# DAU_Kupplung_1_phasig_V1_16.net
KiCad netlist of a schematic drawn in Altium Designer
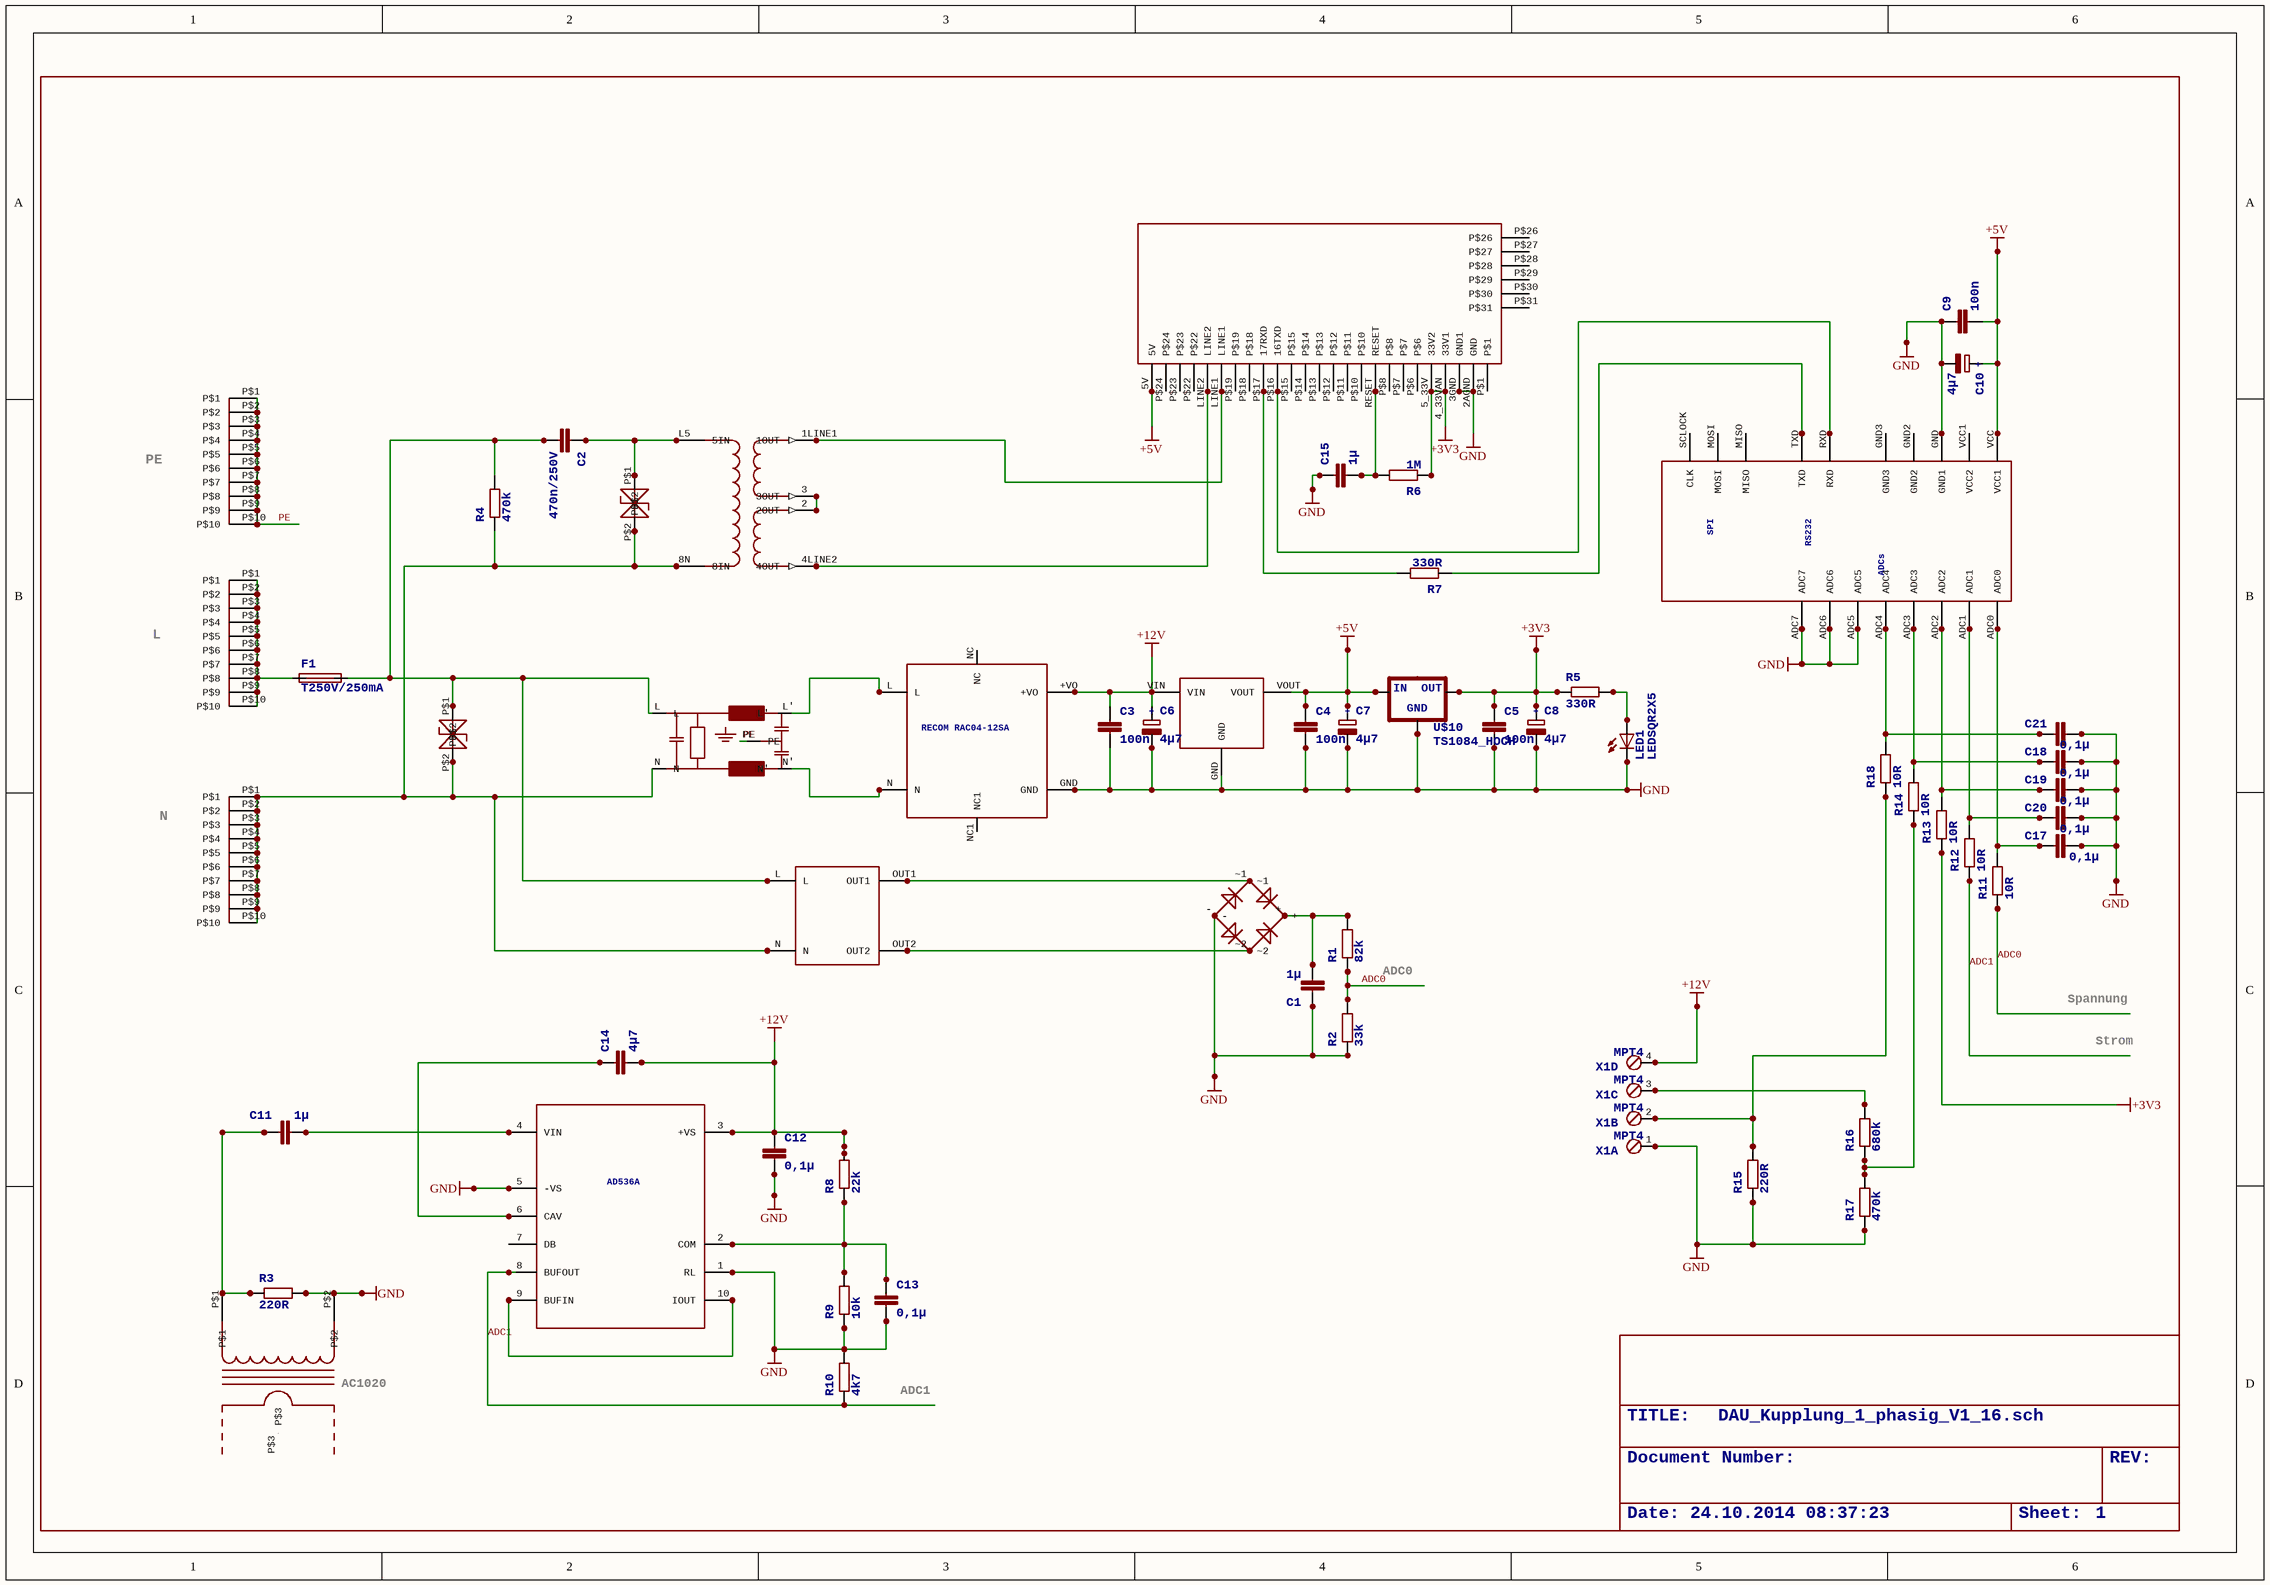
[diagram p0: DAU_Kupplung_1_phasig_V1_16.SchDoc]

(export (version "E")
  (design (tool "Eeschema 10.0.6"))
  (components
    (comp (ref "AC1020") (value "AC1010") (footprint "AC1010") (libsource (lib "ADS") (part "AC1010")))
    (comp (ref "C1")
      (value "1µ")
      (footprint "C2.5-3")
      (description "<B>CAPACITOR</B><p>\nnaming: grid - package width")
      (libsource (lib "capacitor-wima") (part "C2,5-3"))
    )
    (comp (ref "C2")
      (value "470n/250V")
      (footprint "C150-072X183")
      (description "<B>CAPACITOR</B>, European symbol")
      (libsource (lib "resistor") (part "C-EU150-072X183"))
    )
    (comp (ref "C3")
      (value "100n")
      (footprint "C0805")
      (description "<B>CAPACITOR</B>, European symbol")
      (libsource (lib "") (part "C-EUC0805_1"))
    )
    (comp (ref "C4")
      (value "100n")
      (footprint "C0805")
      (description "<B>CAPACITOR</B>, European symbol")
      (libsource (lib "") (part "C-EUC0805_1"))
    )
    (comp (ref "C5")
      (value "100n")
      (footprint "C0805")
      (description "<B>CAPACITOR</B>, European symbol")
      (libsource (lib "") (part "C-EUC0805_1"))
    )
    (comp (ref "C6")
      (value "4µ7")
      (footprint "E2-4")
      (description "<B>POLARIZED CAPACITOR</B>, European symbol")
      (fields (field (name "+") "+"))
      (libsource (lib "rcl") (part "CPOL-EUE2-4"))
    )
    (comp (ref "C7")
      (value "4µ7")
      (footprint "E2-4")
      (description "<B>POLARIZED CAPACITOR</B>, European symbol")
      (fields (field (name "+") "+"))
      (libsource (lib "rcl") (part "CPOL-EUE2-4"))
    )
    (comp (ref "C8")
      (value "4µ7")
      (footprint "E2-4")
      (description "<B>POLARIZED CAPACITOR</B>, European symbol")
      (fields (field (name "+") "+"))
      (libsource (lib "rcl") (part "CPOL-EUE2-4"))
    )
    (comp (ref "C9")
      (value "100n")
      (footprint "C0805")
      (description "<B>CAPACITOR</B>, European symbol")
      (libsource (lib "") (part "C-EUC0805_1"))
    )
    (comp (ref "C10")
      (value "4µ7")
      (footprint "E2-4")
      (description "<B>POLARIZED CAPACITOR</B>, European symbol")
      (fields (field (name "+") "+"))
      (libsource (lib "") (part "CPOL-EUE2-4_1"))
    )
    (comp (ref "C11")
      (value "1µ")
      (footprint "C0805")
      (description "<B>CAPACITOR</B>, European symbol")
      (libsource (lib "") (part "C-EUC0805_1"))
    )
    (comp (ref "C12")
      (value "0,1µ")
      (footprint "C0805")
      (description "<B>CAPACITOR</B>, European symbol")
      (libsource (lib "rcl") (part "C-EUC0805"))
    )
    (comp (ref "C13")
      (value "0,1µ")
      (footprint "C0805")
      (description "<B>CAPACITOR</B>, European symbol")
      (libsource (lib "rcl") (part "C-EUC0805"))
    )
    (comp (ref "C14")
      (value "4µ7")
      (footprint "C0805")
      (description "<B>CAPACITOR</B>, European symbol")
      (libsource (lib "") (part "C-EUC0805_1"))
    )
    (comp (ref "C15")
      (value "1µ")
      (footprint "C0805")
      (description "<B>CAPACITOR</B>, European symbol")
      (libsource (lib "resistor") (part "C-EUC0805"))
    )
    (comp (ref "C17")
      (value "0,1µ")
      (footprint "C0805")
      (description "<B>CAPACITOR</B>, European symbol")
      (libsource (lib "resistor") (part "C-EUC0805"))
    )
    (comp (ref "C18")
      (value "0,1µ")
      (footprint "C0805")
      (description "<B>CAPACITOR</B>, European symbol")
      (libsource (lib "resistor") (part "C-EUC0805"))
    )
    (comp (ref "C19")
      (value "0,1µ")
      (footprint "C0805")
      (description "<B>CAPACITOR</B>, European symbol")
      (libsource (lib "resistor") (part "C-EUC0805"))
    )
    (comp (ref "C20")
      (value "0,1µ")
      (footprint "C0805")
      (description "<B>CAPACITOR</B>, European symbol")
      (libsource (lib "resistor") (part "C-EUC0805"))
    )
    (comp (ref "C21")
      (value "0,1µ")
      (footprint "C0805")
      (description "<B>CAPACITOR</B>, European symbol")
      (libsource (lib "resistor") (part "C-EUC0805"))
    )
    (comp (ref "F1")
      (value "T250V/250mA")
      (footprint "TR5")
      (description "<b>FUSE</b><p>\nWickmann")
      (libsource (lib "fuse") (part "TR5"))
    )
    (comp (ref "L")
      (value "PRINT_CONNECTOR")
      (footprint "FASTON_DOUBLE")
      (libsource (lib "ADS") (part "PRINT_CONNECTOR"))
    )
    (comp (ref "LED1") (value "LEDSQR2X5") (footprint "LED2X5") (libsource (lib "led") (part "LEDSQR2X5")))
    (comp (ref "N")
      (value "PRINT_CONNECTOR")
      (footprint "FASTON_DOUBLE")
      (libsource (lib "ADS") (part "PRINT_CONNECTOR"))
    )
    (comp (ref "PE")
      (value "PRINT_CONNECTOR")
      (footprint "FASTON_DOUBLE")
      (libsource (lib "ADS") (part "PRINT_CONNECTOR"))
    )
    (comp (ref "R1")
      (value "82k")
      (footprint "R1206")
      (description "<B>RESISTOR</B>, European symbol")
      (libsource (lib "resistor") (part "R-EU_R1206"))
    )
    (comp (ref "R2")
      (value "33k")
      (footprint "R1206")
      (description "<B>RESISTOR</B>, European symbol")
      (libsource (lib "resistor") (part "R-EU_R1206"))
    )
    (comp (ref "R3")
      (value "220R")
      (footprint "R1206")
      (description "<B>RESISTOR</B>, European symbol")
      (libsource (lib "resistor") (part "R-EU_R1206"))
    )
    (comp (ref "R4")
      (value "470k")
      (footprint "0204/7")
      (description "<B>RESISTOR</B>, European symbol")
      (libsource (lib "resistor") (part "R-EU_0204/7"))
    )
    (comp (ref "R5")
      (value "330R")
      (footprint "R1206")
      (description "<B>RESISTOR</B>, European symbol")
      (libsource (lib "resistor") (part "R-EU_R1206"))
    )
    (comp (ref "R6")
      (value "1M")
      (footprint "R1206")
      (description "<B>RESISTOR</B>, European symbol")
      (libsource (lib "resistor") (part "R-EU_R1206"))
    )
    (comp (ref "R7")
      (value "330R")
      (footprint "R1206")
      (description "<B>RESISTOR</B>, European symbol")
      (libsource (lib "resistor") (part "R-EU_R1206"))
    )
    (comp (ref "R8")
      (value "22k")
      (footprint "R1206")
      (description "<B>RESISTOR</B>, European symbol")
      (libsource (lib "resistor") (part "R-EU_R1206"))
    )
    (comp (ref "R9")
      (value "10k")
      (footprint "R1206")
      (description "<B>RESISTOR</B>, European symbol")
      (libsource (lib "resistor") (part "R-EU_R1206"))
    )
    (comp (ref "R10")
      (value "4k7")
      (footprint "R1206")
      (description "<B>RESISTOR</B>, European symbol")
      (libsource (lib "resistor") (part "R-EU_R1206"))
    )
    (comp (ref "R11")
      (value "10R")
      (footprint "R1206")
      (description "<B>RESISTOR</B>, European symbol")
      (libsource (lib "resistor") (part "R-EU_R1206"))
    )
    (comp (ref "R12")
      (value "10R")
      (footprint "R1206")
      (description "<B>RESISTOR</B>, European symbol")
      (libsource (lib "resistor") (part "R-EU_R1206"))
    )
    (comp (ref "R13")
      (value "10R")
      (footprint "R1206")
      (description "<B>RESISTOR</B>, European symbol")
      (libsource (lib "resistor") (part "R-EU_R1206"))
    )
    (comp (ref "R14")
      (value "10R")
      (footprint "R1206")
      (description "<B>RESISTOR</B>, European symbol")
      (libsource (lib "resistor") (part "R-EU_R1206"))
    )
    (comp (ref "R15")
      (value "220R")
      (footprint "R1206")
      (description "<B>RESISTOR</B>, European symbol")
      (libsource (lib "resistor") (part "R-EU_R1206"))
    )
    (comp (ref "R16")
      (value "680k")
      (footprint "R1206")
      (description "<B>RESISTOR</B>, European symbol")
      (libsource (lib "resistor") (part "R-EU_R1206"))
    )
    (comp (ref "R17")
      (value "470k")
      (footprint "R1206")
      (description "<B>RESISTOR</B>, European symbol")
      (libsource (lib "resistor") (part "R-EU_R1206"))
    )
    (comp (ref "R18")
      (value "10R")
      (footprint "R1206")
      (description "<B>RESISTOR</B>, European symbol")
      (libsource (lib "resistor") (part "R-EU_R1206"))
    )
    (comp (ref "U$1")
      (value "RECOM_RAC04_12SA")
      (footprint "RAC04_12SA")
      (fields (field (name "RECOM RAC04-12SA") "RECOM RAC04-12SA"))
      (libsource (lib "ADS") (part "RECOM_RAC04_12SA"))
    )
    (comp (ref "U$2")
      (value "SICHERHEITSTRAFO")
      (footprint "TRAFO_0,35VA")
      (libsource (lib "ADS") (part "SICHERHEITSTRAFO"))
    )
    (comp (ref "U$3")
      (value "ADUC831_MINIMUM")
      (footprint "ADUC_MINIMUM")
      (fields (field (name "SPI") "SPI") (field (name "RS232") "RS232") (field (name "ADCS") "ADCs"))
      (libsource (lib "ADS_ADUCBoards") (part "ADUC831_MINIMUM"))
    )
    (comp (ref "U$4") (value "IT800") (footprint "IT800") (libsource (lib "ADS") (part "IT800")))
    (comp (ref "U$5")
      (value "PLC_UEBERTRAGER_V2")
      (footprint "PLC-UEBERTRAGER_V2")
      (libsource (lib "ADS1") (part "PLC_UEBERTRAGER_V2"))
    )
    (comp (ref "U$6")
      (value "NETZFILTER_05_A")
      (footprint "NETZFILTER")
      (libsource (lib "ADS") (part "NETZFILTER_05_A"))
    )
    (comp (ref "U$7")
      (value "AD536")
      (footprint "TO100_10PIN")
      (fields (field (name "AD536A") "AD536A"))
      (libsource (lib "ADS") (part "AD536"))
    )
    (comp (ref "U$8") (value "RECTIFIER") (footprint "RECTIFIER") (libsource (lib "ADS") (part "RECTIFIER")))
    (comp (ref "U$9") (value "TSV") (footprint "TSV") (libsource (lib "ADS") (part "TSV")))
    (comp (ref "U$10")
      (value "TS1084_HOCH")
      (footprint "TS1084_HOCH")
      (fields (field (name "GND") "GND") (field (name "IN") "IN") (field (name "OUT") "OUT"))
      (libsource (lib "ADS") (part "TS1084_HOCH"))
    )
    (comp (ref "U$11")
      (value "RECOM_785_05")
      (footprint "RECOM785X")
      (libsource (lib "ADS") (part "RECOM_785_05"))
    )
    (comp (ref "U$12") (value "TSV") (footprint "TSV") (libsource (lib "ADS") (part "TSV")))
    (comp (ref "X1")
      (value "MPT4")
      (footprint "4POL254")
      (description "<b>PHOENIX CONNECTOR</b>")
      (libsource (lib "con-phoenix-254") (part "MPT4"))
    )
  )
  (nets
    (net (code "1") (name "+3V3") (class "Default")
      (node (ref "C5") (pin "1") (pinfunction "1_1") (pintype "passive"))
      (node (ref "C8") (pin "+") (pinfunction "+_+") (pintype "passive"))
      (node (ref "R13") (pin "1") (pinfunction "1_1") (pintype "passive"))
      (node (ref "R5") (pin "1") (pinfunction "1_1") (pintype "passive"))
      (node (ref "R6") (pin "1") (pinfunction "1_1") (pintype "passive"))
      (node (ref "U$10") (pin "OUT") (pinfunction "OUT_OUT") (pintype "passive"))
      (node (ref "U$4") (pin "4_33VAN") (pinfunction "33V1_4_33VAN") (pintype "passive"))
      (node (ref "U$4") (pin "5_33V") (pinfunction "33V2_5_33V") (pintype "passive"))
    )
    (net (code "2") (name "+5V") (class "Default")
      (node (ref "C10") (pin "+") (pinfunction "+_+") (pintype "passive"))
      (node (ref "C4") (pin "1") (pinfunction "1_1") (pintype "passive"))
      (node (ref "C7") (pin "+") (pinfunction "+_+") (pintype "passive"))
      (node (ref "C9") (pin "2") (pinfunction "2_2") (pintype "passive"))
      (node (ref "U$10") (pin "IN") (pinfunction "IN_IN") (pintype "passive"))
      (node (ref "U$11") (pin "VOUT") (pinfunction "VOUT_VOUT") (pintype "passive"))
      (node (ref "U$3") (pin "VCC") (pinfunction "VCC1_VCC") (pintype "passive"))
      (node (ref "U$4") (pin "5V") (pinfunction "5V_5V") (pintype "passive"))
    )
    (net (code "3") (name "+12V") (class "Default")
      (node (ref "C12") (pin "1") (pinfunction "1_1") (pintype "passive"))
      (node (ref "C14") (pin "2") (pinfunction "2_2") (pintype "passive"))
      (node (ref "C3") (pin "1") (pinfunction "1_1") (pintype "passive"))
      (node (ref "C6") (pin "+") (pinfunction "+_+") (pintype "passive"))
      (node (ref "R8") (pin "2") (pinfunction "2_2") (pintype "passive"))
      (node (ref "U$1") (pin "+VO") (pinfunction "+VO_+VO") (pintype "passive"))
      (node (ref "U$11") (pin "VIN") (pinfunction "VIN_VIN") (pintype "passive"))
      (node (ref "U$7") (pin "3") (pinfunction "+VS_3") (pintype "passive"))
      (node (ref "X1") (pin "4") (pinfunction "1_4") (pintype "passive"))
    )
    (net (code "4") (name "/ADC0") (class "Default")
      (node (ref "R1") (pin "1") (pinfunction "1_1") (pintype "passive"))
      (node (ref "R11") (pin "1") (pinfunction "1_1") (pintype "passive"))
      (node (ref "R2") (pin "2") (pinfunction "2_2") (pintype "passive"))
    )
    (net (code "5") (name "/ADC1") (class "Default")
      (node (ref "R10") (pin "1") (pinfunction "1_1") (pintype "passive"))
      (node (ref "R12") (pin "1") (pinfunction "1_1") (pintype "passive"))
      (node (ref "U$7") (pin "8") (pinfunction "BUFOUT_8") (pintype "passive"))
    )
    (net (code "6") (name "/PE") (class "Default")
      (node (ref "PE") (pin "P$1") (pinfunction "P$1_P$1") (pintype "passive"))
      (node (ref "PE") (pin "P$10") (pinfunction "P$10_P$10") (pintype "passive"))
      (node (ref "PE") (pin "P$2") (pinfunction "P$2_P$2") (pintype "passive"))
      (node (ref "PE") (pin "P$3") (pinfunction "P$3_P$3") (pintype "passive"))
      (node (ref "PE") (pin "P$4") (pinfunction "P$4_P$4") (pintype "passive"))
      (node (ref "PE") (pin "P$5") (pinfunction "P$5_P$5") (pintype "passive"))
      (node (ref "PE") (pin "P$6") (pinfunction "P$6_P$6") (pintype "passive"))
      (node (ref "PE") (pin "P$7") (pinfunction "P$7_P$7") (pintype "passive"))
      (node (ref "PE") (pin "P$8") (pinfunction "P$8_P$8") (pintype "passive"))
      (node (ref "PE") (pin "P$9") (pinfunction "P$9_P$9") (pintype "passive"))
      (node (ref "U$6") (pin "PE") (pinfunction "PE_PE") (pintype "passive"))
    )
    (net (code "7") (name "GND") (class "Default")
      (node (ref "AC1020") (pin "P$2") (pinfunction "P$2_P$2") (pintype "passive"))
      (node (ref "C1") (pin "1") (pinfunction "1_1") (pintype "passive"))
      (node (ref "C10") (pin "-") (pinfunction "-_-") (pintype "passive"))
      (node (ref "C12") (pin "2") (pinfunction "2_2") (pintype "passive"))
      (node (ref "C13") (pin "2") (pinfunction "2_2") (pintype "passive"))
      (node (ref "C15") (pin "1") (pinfunction "1_1") (pintype "passive"))
      (node (ref "C17") (pin "2") (pinfunction "2_2") (pintype "passive"))
      (node (ref "C18") (pin "2") (pinfunction "2_2") (pintype "passive"))
      (node (ref "C19") (pin "2") (pinfunction "2_2") (pintype "passive"))
      (node (ref "C20") (pin "2") (pinfunction "2_2") (pintype "passive"))
      (node (ref "C21") (pin "2") (pinfunction "2_2") (pintype "passive"))
      (node (ref "C3") (pin "2") (pinfunction "2_2") (pintype "passive"))
      (node (ref "C4") (pin "2") (pinfunction "2_2") (pintype "passive"))
      (node (ref "C5") (pin "2") (pinfunction "2_2") (pintype "passive"))
      (node (ref "C6") (pin "-") (pinfunction "-_-") (pintype "passive"))
      (node (ref "C7") (pin "-") (pinfunction "-_-") (pintype "passive"))
      (node (ref "C8") (pin "-") (pinfunction "-_-") (pintype "passive"))
      (node (ref "C9") (pin "1") (pinfunction "1_1") (pintype "passive"))
      (node (ref "LED1") (pin "K") (pinfunction "C_K") (pintype "passive"))
      (node (ref "R10") (pin "2") (pinfunction "2_2") (pintype "passive"))
      (node (ref "R15") (pin "1") (pinfunction "1_1") (pintype "passive"))
      (node (ref "R17") (pin "1") (pinfunction "1_1") (pintype "passive"))
      (node (ref "R2") (pin "1") (pinfunction "1_1") (pintype "passive"))
      (node (ref "R3") (pin "2") (pinfunction "2_2") (pintype "passive"))
      (node (ref "R9") (pin "1") (pinfunction "1_1") (pintype "passive"))
      (node (ref "U$1") (pin "GND") (pinfunction "GND_GND") (pintype "passive"))
      (node (ref "U$10") (pin "GND") (pinfunction "GND_GND") (pintype "passive"))
      (node (ref "U$11") (pin "GND") (pinfunction "GND_GND") (pintype "passive"))
      (node (ref "U$3") (pin "ADC5") (pinfunction "ADC5_ADC5") (pintype "passive"))
      (node (ref "U$3") (pin "ADC6") (pinfunction "ADC6_ADC6") (pintype "passive"))
      (node (ref "U$3") (pin "ADC7") (pinfunction "ADC7_ADC7") (pintype "passive"))
      (node (ref "U$3") (pin "GND") (pinfunction "GND1_GND") (pintype "passive"))
      (node (ref "U$4") (pin "2AGND") (pinfunction "GND_2AGND") (pintype "passive"))
      (node (ref "U$4") (pin "3GND") (pinfunction "GND1_3GND") (pintype "passive"))
      (node (ref "U$7") (pin "1") (pinfunction "RL_1") (pintype "passive"))
      (node (ref "U$7") (pin "5") (pinfunction "-VS_5") (pintype "passive"))
      (node (ref "U$8") (pin "-") (pinfunction "-_-") (pintype "passive"))
      (node (ref "X1") (pin "1") (pinfunction "1_1") (pintype "passive"))
    )
    (net (code "8") (name "Net-(AC1020-PadP$1)") (class "Default")
      (node (ref "AC1020") (pin "P$1") (pinfunction "P$1_P$1") (pintype "passive"))
      (node (ref "C11") (pin "1") (pinfunction "1_1") (pintype "passive"))
      (node (ref "R3") (pin "1") (pinfunction "1_1") (pintype "passive"))
    )
    (net (code "9") (name "Net-(C1-Pad2)") (class "Default")
      (node (ref "C1") (pin "2") (pinfunction "2_2") (pintype "passive"))
      (node (ref "R1") (pin "2") (pinfunction "2_2") (pintype "passive"))
      (node (ref "U$8") (pin "+") (pinfunction "+_+") (pintype "passive"))
    )
    (net (code "10") (name "Net-(C2-Pad2)") (class "Default")
      (node (ref "C2") (pin "2") (pinfunction "2_2") (pintype "passive"))
      (node (ref "F1") (pin "2") (pinfunction "2_2") (pintype "passive"))
      (node (ref "R4") (pin "2") (pinfunction "2_2") (pintype "passive"))
      (node (ref "U$2") (pin "L") (pinfunction "L_L") (pintype "passive"))
      (node (ref "U$6") (pin "L") (pinfunction "L_L") (pintype "passive"))
      (node (ref "U$9") (pin "P$1") (pinfunction "P$1_P$1") (pintype "passive"))
    )
    (net (code "11") (name "Net-(C15-Pad2)") (class "Default")
      (node (ref "C15") (pin "2") (pinfunction "2_2") (pintype "passive"))
      (node (ref "R6") (pin "2") (pinfunction "2_2") (pintype "passive"))
      (node (ref "U$4") (pin "RESET") (pinfunction "RESET_RESET") (pintype "passive"))
    )
    (net (code "12") (name "Net-(C17-Pad1)") (class "Default")
      (node (ref "C17") (pin "1") (pinfunction "1_1") (pintype "passive"))
      (node (ref "R11") (pin "2") (pinfunction "2_2") (pintype "passive"))
      (node (ref "U$3") (pin "ADC0") (pinfunction "ADC0_ADC0") (pintype "passive"))
    )
    (net (code "13") (name "Net-(C18-Pad1)") (class "Default")
      (node (ref "C18") (pin "1") (pinfunction "1_1") (pintype "passive"))
      (node (ref "R14") (pin "2") (pinfunction "2_2") (pintype "passive"))
      (node (ref "U$3") (pin "ADC3") (pinfunction "ADC3_ADC3") (pintype "passive"))
    )
    (net (code "14") (name "Net-(C19-Pad1)") (class "Default")
      (node (ref "C19") (pin "1") (pinfunction "1_1") (pintype "passive"))
      (node (ref "R13") (pin "2") (pinfunction "2_2") (pintype "passive"))
      (node (ref "U$3") (pin "ADC2") (pinfunction "ADC2_ADC2") (pintype "passive"))
    )
    (net (code "15") (name "Net-(C20-Pad1)") (class "Default")
      (node (ref "C20") (pin "1") (pinfunction "1_1") (pintype "passive"))
      (node (ref "R12") (pin "2") (pinfunction "2_2") (pintype "passive"))
      (node (ref "U$3") (pin "ADC1") (pinfunction "ADC1_ADC1") (pintype "passive"))
    )
    (net (code "16") (name "Net-(C21-Pad1)") (class "Default")
      (node (ref "C21") (pin "1") (pinfunction "1_1") (pintype "passive"))
      (node (ref "R18") (pin "2") (pinfunction "2_2") (pintype "passive"))
      (node (ref "U$3") (pin "ADC4") (pinfunction "ADC4_ADC4") (pintype "passive"))
    )
    (net (code "17") (name "Net-(F1-Pad1)") (class "Default")
      (node (ref "F1") (pin "1") (pinfunction "1_1") (pintype "passive"))
      (node (ref "L") (pin "P$1") (pinfunction "P$1_P$1") (pintype "passive"))
      (node (ref "L") (pin "P$10") (pinfunction "P$10_P$10") (pintype "passive"))
      (node (ref "L") (pin "P$2") (pinfunction "P$2_P$2") (pintype "passive"))
      (node (ref "L") (pin "P$3") (pinfunction "P$3_P$3") (pintype "passive"))
      (node (ref "L") (pin "P$4") (pinfunction "P$4_P$4") (pintype "passive"))
      (node (ref "L") (pin "P$5") (pinfunction "P$5_P$5") (pintype "passive"))
      (node (ref "L") (pin "P$6") (pinfunction "P$6_P$6") (pintype "passive"))
      (node (ref "L") (pin "P$7") (pinfunction "P$7_P$7") (pintype "passive"))
      (node (ref "L") (pin "P$8") (pinfunction "P$8_P$8") (pintype "passive"))
      (node (ref "L") (pin "P$9") (pinfunction "P$9_P$9") (pintype "passive"))
    )
    (net (code "18") (name "Net-(LED1-PadA)") (class "Default")
      (node (ref "LED1") (pin "A") (pinfunction "A_A") (pintype "passive"))
      (node (ref "R5") (pin "2") (pinfunction "2_2") (pintype "passive"))
    )
    (net (code "19") (name "Net-(R7-Pad1)") (class "Default")
      (node (ref "R7") (pin "1") (pinfunction "1_1") (pintype "passive"))
      (node (ref "U$3") (pin "TXD") (pinfunction "TXD_TXD") (pintype "passive"))
    )
    (net (code "20") (name "Net-(R14-Pad1)") (class "Default")
      (node (ref "R14") (pin "1") (pinfunction "1_1") (pintype "passive"))
      (node (ref "R16") (pin "1") (pinfunction "1_1") (pintype "passive"))
      (node (ref "R17") (pin "2") (pinfunction "2_2") (pintype "passive"))
    )
    (net (code "21") (name "Net-(U$1-PadL)") (class "Default")
      (node (ref "U$1") (pin "L") (pinfunction "L_L") (pintype "passive"))
      (node (ref "U$6") (pin "L'") (pinfunction "L'_L'") (pintype "passive"))
    )
    (net (code "22") (name "Net-(U$1-PadN)") (class "Default")
      (node (ref "U$1") (pin "N") (pinfunction "N_N") (pintype "passive"))
      (node (ref "U$6") (pin "N'") (pinfunction "N'_N'") (pintype "passive"))
    )
    (net (code "23") (name "Net-(U$2-PadOUT1)") (class "Default")
      (node (ref "U$2") (pin "OUT1") (pinfunction "OUT1_OUT1") (pintype "passive"))
      (node (ref "U$8") (pin "~1") (pinfunction "~1_~1") (pintype "passive"))
    )
    (net (code "24") (name "Net-(U$2-PadOUT2)") (class "Default")
      (node (ref "U$2") (pin "OUT2") (pinfunction "OUT2_OUT2") (pintype "passive"))
      (node (ref "U$8") (pin "~2") (pinfunction "~2_~2") (pintype "passive"))
    )
    (net (code "25") (name "Net-(U$4-16TXD)") (class "Default")
      (node (ref "U$3") (pin "RXD") (pinfunction "RXD_RXD") (pintype "passive"))
      (node (ref "U$4") (pin "P$16") (pinfunction "16TXD_P$16") (pintype "passive"))
    )
    (net (code "26") (name "Net-(U$4-17RXD)") (class "Default")
      (node (ref "R7") (pin "2") (pinfunction "2_2") (pintype "passive"))
      (node (ref "U$4") (pin "P$17") (pinfunction "17RXD_P$17") (pintype "passive"))
    )
    (net (code "27") (name "Net-(U$5-1OUT)") (class "Default")
      (node (ref "U$4") (pin "LINE1") (pinfunction "LINE1_LINE1") (pintype "passive"))
      (node (ref "U$5") (pin "1LINE1") (pinfunction "1OUT_1LINE1") (pintype "output"))
    )
    (net (code "28") (name "Net-(U$5-2OUT)") (class "Default")
      (node (ref "U$5") (pin "2") (pinfunction "2OUT_2") (pintype "output"))
      (node (ref "U$5") (pin "3") (pinfunction "3OUT_3") (pintype "output"))
    )
    (net (code "29") (name "Net-(U$5-4OUT)") (class "Default")
      (node (ref "U$4") (pin "LINE2") (pinfunction "LINE2_LINE2") (pintype "passive"))
      (node (ref "U$5") (pin "4LINE2") (pinfunction "4OUT_4LINE2") (pintype "output"))
    )
    (net (code "30") (name "Net-(U$5-5IN)") (class "Default")
      (node (ref "C2") (pin "1") (pinfunction "1_1") (pintype "passive"))
      (node (ref "U$12") (pin "P$1") (pinfunction "P$1_P$1") (pintype "passive"))
      (node (ref "U$5") (pin "L5") (pinfunction "5IN_L5") (pintype "passive"))
    )
    (net (code "31") (name "Net-(U$5-8IN)") (class "Default")
      (node (ref "N") (pin "P$1") (pinfunction "P$1_P$1") (pintype "passive"))
      (node (ref "N") (pin "P$10") (pinfunction "P$10_P$10") (pintype "passive"))
      (node (ref "N") (pin "P$2") (pinfunction "P$2_P$2") (pintype "passive"))
      (node (ref "N") (pin "P$3") (pinfunction "P$3_P$3") (pintype "passive"))
      (node (ref "N") (pin "P$4") (pinfunction "P$4_P$4") (pintype "passive"))
      (node (ref "N") (pin "P$5") (pinfunction "P$5_P$5") (pintype "passive"))
      (node (ref "N") (pin "P$6") (pinfunction "P$6_P$6") (pintype "passive"))
      (node (ref "N") (pin "P$7") (pinfunction "P$7_P$7") (pintype "passive"))
      (node (ref "N") (pin "P$8") (pinfunction "P$8_P$8") (pintype "passive"))
      (node (ref "N") (pin "P$9") (pinfunction "P$9_P$9") (pintype "passive"))
      (node (ref "R4") (pin "1") (pinfunction "1_1") (pintype "passive"))
      (node (ref "U$12") (pin "P$2") (pinfunction "P$2_P$2") (pintype "passive"))
      (node (ref "U$2") (pin "N") (pinfunction "N_N") (pintype "passive"))
      (node (ref "U$5") (pin "8N") (pinfunction "8IN_8N") (pintype "passive"))
      (node (ref "U$6") (pin "N") (pinfunction "N_N") (pintype "passive"))
      (node (ref "U$9") (pin "P$2") (pinfunction "P$2_P$2") (pintype "passive"))
    )
    (net (code "32") (name "Net-(U$7-BUFIN)") (class "Default")
      (node (ref "U$7") (pin "10") (pinfunction "IOUT_10") (pintype "passive"))
      (node (ref "U$7") (pin "9") (pinfunction "BUFIN_9") (pintype "passive"))
    )
    (net (code "33") (name "Net-(U$7-CAV)") (class "Default")
      (node (ref "C14") (pin "1") (pinfunction "1_1") (pintype "passive"))
      (node (ref "U$7") (pin "6") (pinfunction "CAV_6") (pintype "passive"))
    )
    (net (code "34") (name "Net-(U$7-COM)") (class "Default")
      (node (ref "C13") (pin "1") (pinfunction "1_1") (pintype "passive"))
      (node (ref "R8") (pin "1") (pinfunction "1_1") (pintype "passive"))
      (node (ref "R9") (pin "2") (pinfunction "2_2") (pintype "passive"))
      (node (ref "U$7") (pin "2") (pinfunction "COM_2") (pintype "passive"))
    )
    (net (code "35") (name "Net-(U$7-VIN)") (class "Default")
      (node (ref "C11") (pin "2") (pinfunction "2_2") (pintype "passive"))
      (node (ref "U$7") (pin "4") (pinfunction "VIN_4") (pintype "passive"))
    )
    (net (code "36") (name "Net-(X1B-1)") (class "Default")
      (node (ref "R15") (pin "2") (pinfunction "2_2") (pintype "passive"))
      (node (ref "R18") (pin "1") (pinfunction "1_1") (pintype "passive"))
      (node (ref "X1") (pin "2") (pinfunction "1_2") (pintype "passive"))
    )
    (net (code "37") (name "Net-(X1C-1)") (class "Default")
      (node (ref "R16") (pin "2") (pinfunction "2_2") (pintype "passive"))
      (node (ref "X1") (pin "3") (pinfunction "1_3") (pintype "passive"))
    )
    (net (code "38") (name "unconnected-(AC1020-PadP$3)") (class "Default")
      (node (ref "AC1020") (pin "P$3") (pinfunction "P$3_P$3") (pintype "passive"))
    )
    (net (code "39") (name "unconnected-(U$1-PadNC)") (class "Default")
      (node (ref "U$1") (pin "NC") (pinfunction "NC_NC") (pintype "passive"))
    )
    (net (code "40") (name "unconnected-(U$1-PadNC1)") (class "Default")
      (node (ref "U$1") (pin "NC1") (pinfunction "NC1_NC1") (pintype "passive"))
    )
    (net (code "41") (name "unconnected-(U$3-CLK-PadSCLOCK)") (class "Default")
      (node (ref "U$3") (pin "SCLOCK") (pinfunction "CLK_SCLOCK") (pintype "passive"))
    )
    (net (code "42") (name "unconnected-(U$3-PadGND2)") (class "Default")
      (node (ref "U$3") (pin "GND2") (pinfunction "GND2_GND2") (pintype "passive"))
    )
    (net (code "43") (name "unconnected-(U$3-PadGND3)") (class "Default")
      (node (ref "U$3") (pin "GND3") (pinfunction "GND3_GND3") (pintype "passive"))
    )
    (net (code "44") (name "unconnected-(U$3-PadMISO)") (class "Default")
      (node (ref "U$3") (pin "MISO") (pinfunction "MISO_MISO") (pintype "passive"))
    )
    (net (code "45") (name "unconnected-(U$3-PadMOSI)") (class "Default")
      (node (ref "U$3") (pin "MOSI") (pinfunction "MOSI_MOSI") (pintype "passive"))
    )
    (net (code "46") (name "unconnected-(U$3-VCC2-PadVCC1)") (class "Default")
      (node (ref "U$3") (pin "VCC1") (pinfunction "VCC2_VCC1") (pintype "passive"))
    )
    (net (code "47") (name "unconnected-(U$4-PadP$1)") (class "Default")
      (node (ref "U$4") (pin "P$1") (pinfunction "P$1_P$1") (pintype "passive"))
    )
    (net (code "48") (name "unconnected-(U$4-PadP$6)") (class "Default")
      (node (ref "U$4") (pin "P$6") (pinfunction "P$6_P$6") (pintype "passive"))
    )
    (net (code "49") (name "unconnected-(U$4-PadP$7)") (class "Default")
      (node (ref "U$4") (pin "P$7") (pinfunction "P$7_P$7") (pintype "passive"))
    )
    (net (code "50") (name "unconnected-(U$4-PadP$8)") (class "Default")
      (node (ref "U$4") (pin "P$8") (pinfunction "P$8_P$8") (pintype "passive"))
    )
    (net (code "51") (name "unconnected-(U$4-PadP$10)") (class "Default")
      (node (ref "U$4") (pin "P$10") (pinfunction "P$10_P$10") (pintype "passive"))
    )
    (net (code "52") (name "unconnected-(U$4-PadP$11)") (class "Default")
      (node (ref "U$4") (pin "P$11") (pinfunction "P$11_P$11") (pintype "passive"))
    )
    (net (code "53") (name "unconnected-(U$4-PadP$12)") (class "Default")
      (node (ref "U$4") (pin "P$12") (pinfunction "P$12_P$12") (pintype "passive"))
    )
    (net (code "54") (name "unconnected-(U$4-PadP$13)") (class "Default")
      (node (ref "U$4") (pin "P$13") (pinfunction "P$13_P$13") (pintype "passive"))
    )
    (net (code "55") (name "unconnected-(U$4-PadP$14)") (class "Default")
      (node (ref "U$4") (pin "P$14") (pinfunction "P$14_P$14") (pintype "passive"))
    )
    (net (code "56") (name "unconnected-(U$4-PadP$15)") (class "Default")
      (node (ref "U$4") (pin "P$15") (pinfunction "P$15_P$15") (pintype "passive"))
    )
    (net (code "57") (name "unconnected-(U$4-PadP$18)") (class "Default")
      (node (ref "U$4") (pin "P$18") (pinfunction "P$18_P$18") (pintype "passive"))
    )
    (net (code "58") (name "unconnected-(U$4-PadP$19)") (class "Default")
      (node (ref "U$4") (pin "P$19") (pinfunction "P$19_P$19") (pintype "passive"))
    )
    (net (code "59") (name "unconnected-(U$4-PadP$22)") (class "Default")
      (node (ref "U$4") (pin "P$22") (pinfunction "P$22_P$22") (pintype "passive"))
    )
    (net (code "60") (name "unconnected-(U$4-PadP$23)") (class "Default")
      (node (ref "U$4") (pin "P$23") (pinfunction "P$23_P$23") (pintype "passive"))
    )
    (net (code "61") (name "unconnected-(U$4-PadP$24)") (class "Default")
      (node (ref "U$4") (pin "P$24") (pinfunction "P$24_P$24") (pintype "passive"))
    )
    (net (code "62") (name "unconnected-(U$4-PadP$26)") (class "Default")
      (node (ref "U$4") (pin "P$26") (pinfunction "P$26_P$26") (pintype "passive"))
    )
    (net (code "63") (name "unconnected-(U$4-PadP$27)") (class "Default")
      (node (ref "U$4") (pin "P$27") (pinfunction "P$27_P$27") (pintype "passive"))
    )
    (net (code "64") (name "unconnected-(U$4-PadP$28)") (class "Default")
      (node (ref "U$4") (pin "P$28") (pinfunction "P$28_P$28") (pintype "passive"))
    )
    (net (code "65") (name "unconnected-(U$4-PadP$29)") (class "Default")
      (node (ref "U$4") (pin "P$29") (pinfunction "P$29_P$29") (pintype "passive"))
    )
    (net (code "66") (name "unconnected-(U$4-PadP$30)") (class "Default")
      (node (ref "U$4") (pin "P$30") (pinfunction "P$30_P$30") (pintype "passive"))
    )
    (net (code "67") (name "unconnected-(U$4-PadP$31)") (class "Default")
      (node (ref "U$4") (pin "P$31") (pinfunction "P$31_P$31") (pintype "passive"))
    )
    (net (code "68") (name "unconnected-(U$7-DB-Pad7)") (class "Default")
      (node (ref "U$7") (pin "7") (pinfunction "DB_7") (pintype "passive"))
    )
  )
)
